# Pg5-Voltage_signal_condtioning.net
KiCad netlist of a schematic drawn in Altium Designer
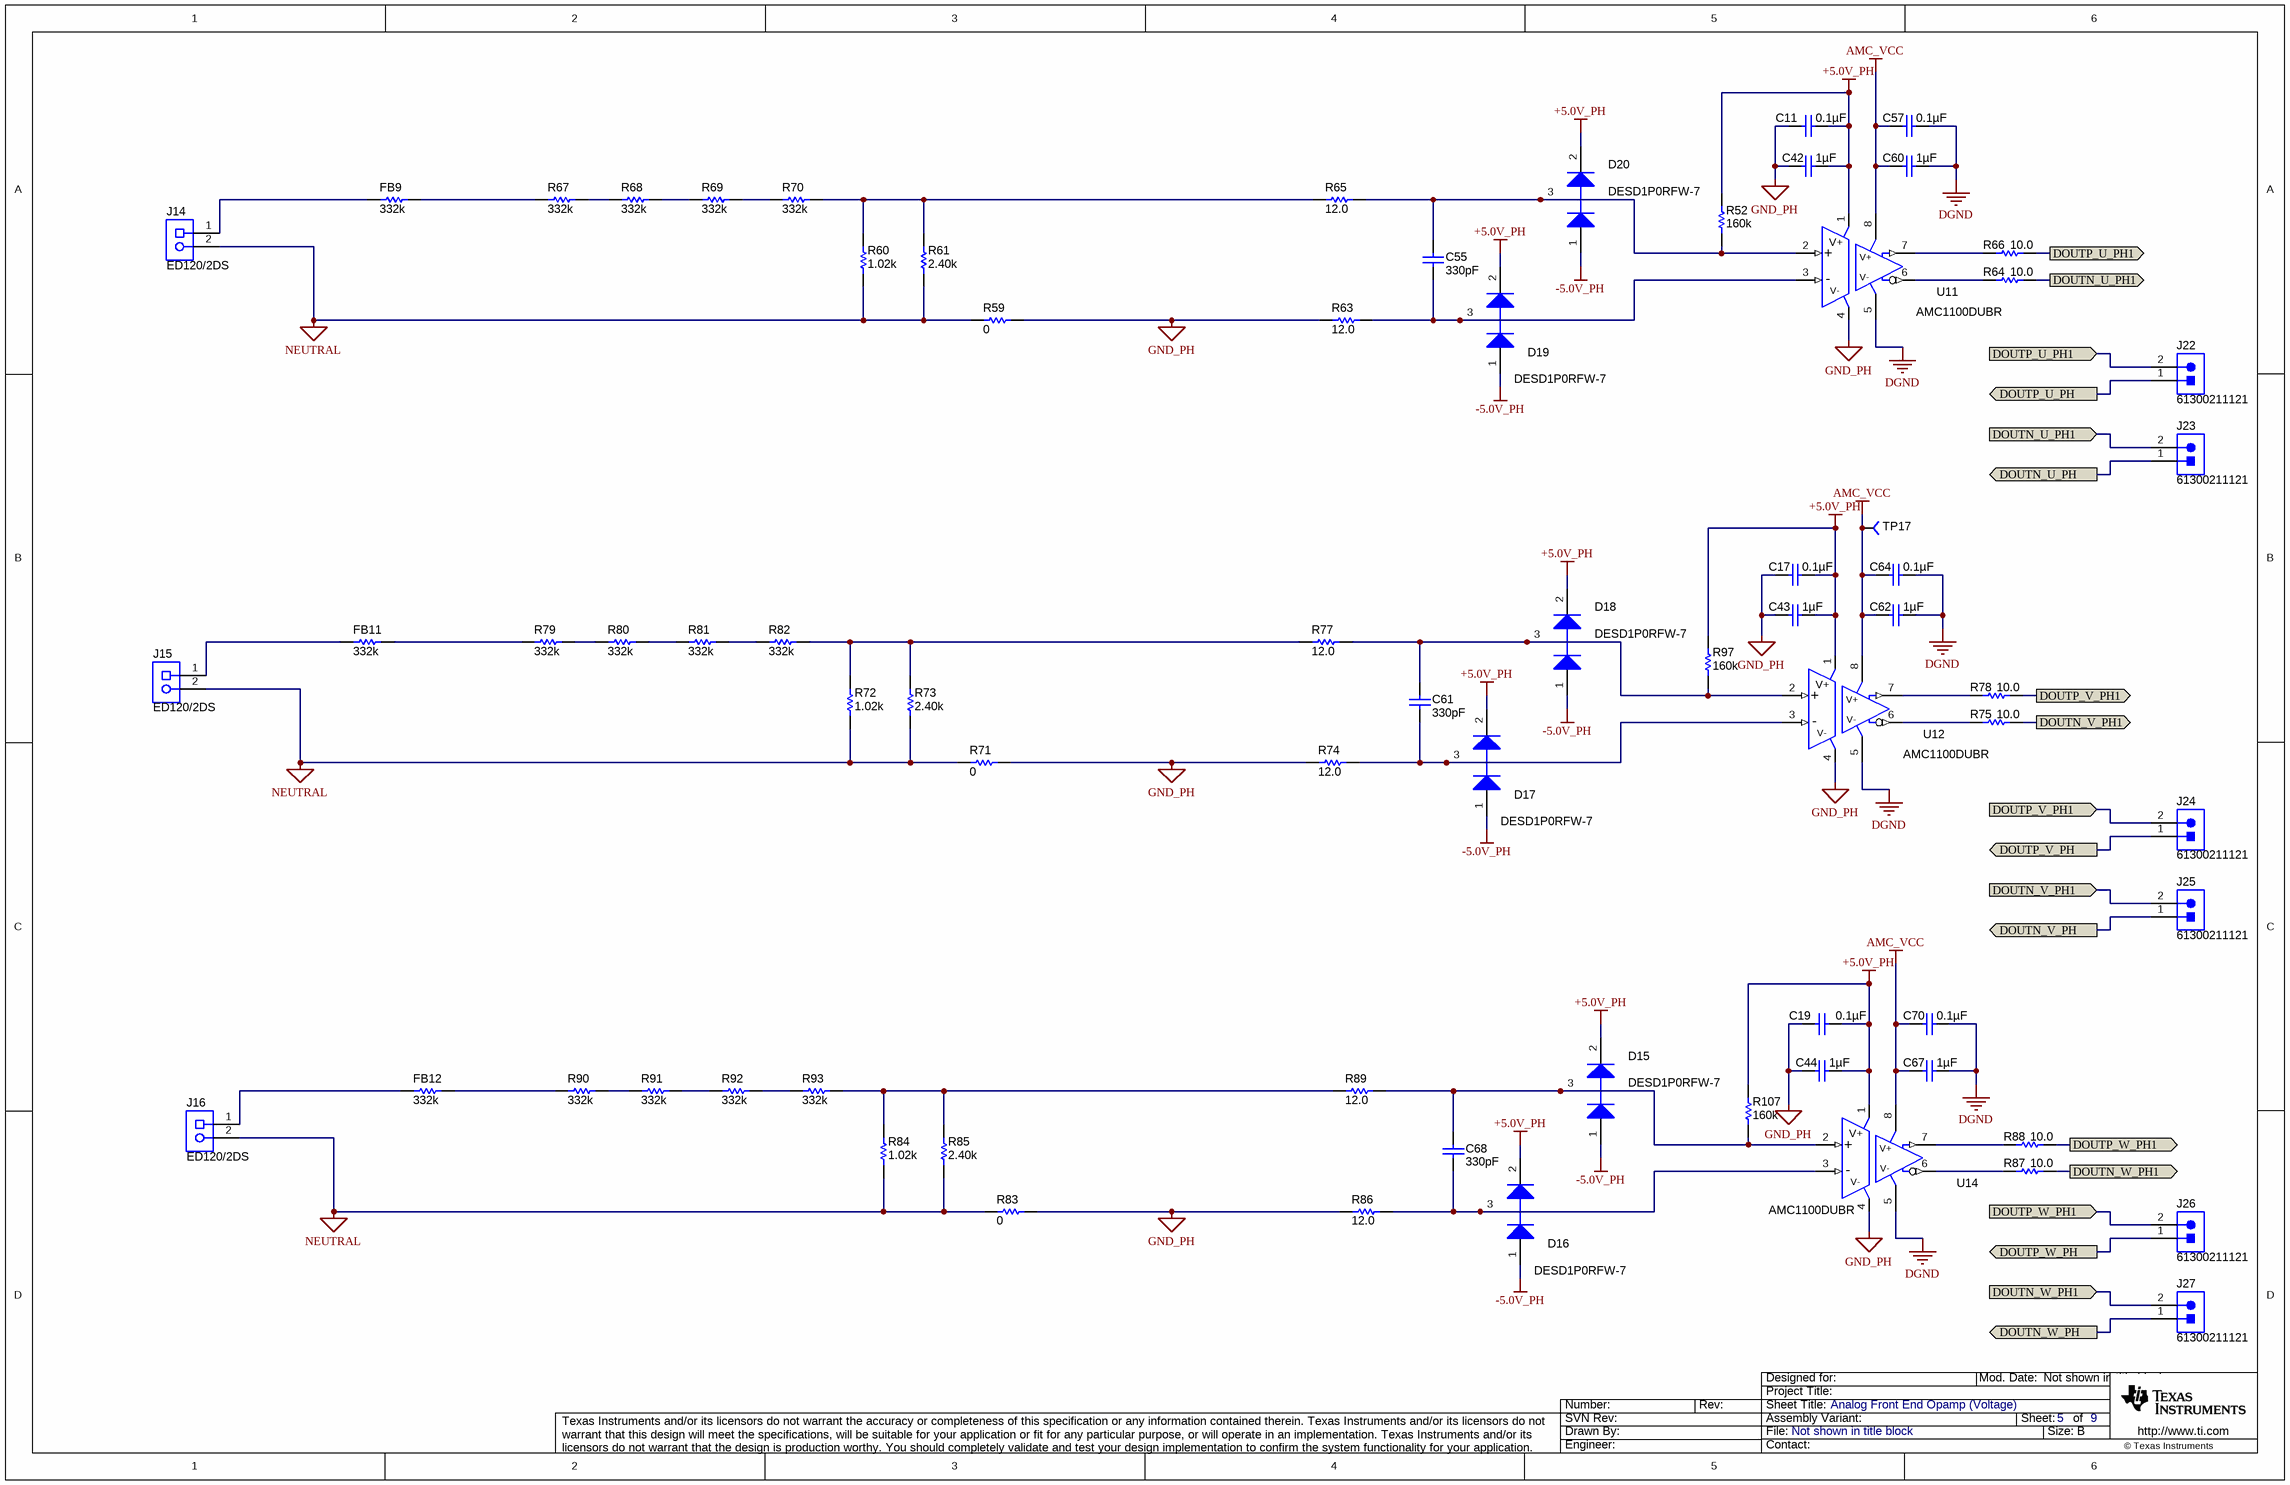
[diagram p0: Pg5-Voltage signal condtioning.SchDoc]

(export (version "E")
  (design (tool "Eeschema 10.0.6"))
  (components
    (comp (ref "C11")
      (value "~")
      (footprint "0603")
      (description "CAP, CERM, 0.1uF, 25V, +/-5%, X7R, 0603")
      (fields
        (field (name "PARTNUMBER") "06033C104JAT2A")
        (field (name "VALUEDISPLAYED") "0.1µF")
        (field (name "MANUFACTURER") "AVX")
        (field (name "PUBLISHER") "Texas Instruments")
      )
      (libsource (lib "Capacitor_Ceramic") (part "06033C104JAT2A"))
    )
    (comp (ref "C17")
      (value "~")
      (footprint "0603")
      (description "CAP, CERM, 0.1uF, 25V, +/-5%, X7R, 0603")
      (fields
        (field (name "PARTNUMBER") "06033C104JAT2A")
        (field (name "VALUEDISPLAYED") "0.1µF")
        (field (name "MANUFACTURER") "AVX")
        (field (name "PUBLISHER") "Texas Instruments")
      )
      (libsource (lib "Capacitor_Ceramic") (part "06033C104JAT2A"))
    )
    (comp (ref "C19")
      (value "~")
      (footprint "0603")
      (description "CAP, CERM, 0.1uF, 25V, +/-5%, X7R, 0603")
      (fields
        (field (name "PARTNUMBER") "06033C104JAT2A")
        (field (name "VALUEDISPLAYED") "0.1µF")
        (field (name "MANUFACTURER") "AVX")
        (field (name "PUBLISHER") "Texas Instruments")
      )
      (libsource (lib "Capacitor_Ceramic") (part "06033C104JAT2A"))
    )
    (comp (ref "C42")
      (value "GRM188R71C105KA12D")
      (footprint "0603")
      (description "CAP, CERM, 1 µF, 16 V, +/- 10%, X7R, 0603")
      (fields
        (field (name "VALUEDISPLAYED") "1µF")
        (field (name "MANUFACTURER") "MuRata")
        (field (name "PUBLISHER") "Texas Instruments")
      )
      (libsource (lib "Capacitor_Ceramic") (part "GRM188R71C105KA12D"))
    )
    (comp (ref "C43")
      (value "GRM188R71C105KA12D")
      (footprint "0603")
      (description "CAP, CERM, 1 µF, 16 V, +/- 10%, X7R, 0603")
      (fields
        (field (name "VALUEDISPLAYED") "1µF")
        (field (name "MANUFACTURER") "MuRata")
        (field (name "PUBLISHER") "Texas Instruments")
      )
      (libsource (lib "Capacitor_Ceramic") (part "GRM188R71C105KA12D"))
    )
    (comp (ref "C44")
      (value "GRM188R71C105KA12D")
      (footprint "0603")
      (description "CAP, CERM, 1 µF, 16 V, +/- 10%, X7R, 0603")
      (fields
        (field (name "VALUEDISPLAYED") "1µF")
        (field (name "MANUFACTURER") "MuRata")
        (field (name "PUBLISHER") "Texas Instruments")
      )
      (libsource (lib "Capacitor_Ceramic") (part "GRM188R71C105KA12D"))
    )
    (comp (ref "C55")
      (value "08055A331KAT2A")
      (footprint "0805_HV")
      (description "CAP, CERM, 330 pF, 50 V, +/- 10%, C0G/NP0, 0805")
      (fields
        (field (name "VALUEDISPLAYED") "330pF")
        (field (name "MANUFACTURER") "AVX")
        (field (name "PUBLISHER") "Texas Instruments")
      )
      (libsource (lib "Capacitor_Ceramic") (part "08055A331KAT2A"))
    )
    (comp (ref "C57")
      (value "~")
      (footprint "0603")
      (description "CAP, CERM, 0.1uF, 25V, +/-5%, X7R, 0603")
      (fields
        (field (name "PARTNUMBER") "06033C104JAT2A")
        (field (name "VALUEDISPLAYED") "0.1µF")
        (field (name "MANUFACTURER") "AVX")
        (field (name "PUBLISHER") "Texas Instruments")
      )
      (libsource (lib "Capacitor_Ceramic") (part "06033C104JAT2A"))
    )
    (comp (ref "C60")
      (value "GRM188R71C105KA12D")
      (footprint "0603")
      (description "CAP, CERM, 1 µF, 16 V, +/- 10%, X7R, 0603")
      (fields
        (field (name "VALUEDISPLAYED") "1µF")
        (field (name "MANUFACTURER") "MuRata")
        (field (name "PUBLISHER") "Texas Instruments")
      )
      (libsource (lib "Capacitor_Ceramic") (part "GRM188R71C105KA12D"))
    )
    (comp (ref "C61")
      (value "08055A331KAT2A")
      (footprint "0805_HV")
      (description "CAP, CERM, 330 pF, 50 V, +/- 10%, C0G/NP0, 0805")
      (fields
        (field (name "VALUEDISPLAYED") "330pF")
        (field (name "MANUFACTURER") "AVX")
        (field (name "PUBLISHER") "Texas Instruments")
      )
      (libsource (lib "Capacitor_Ceramic") (part "08055A331KAT2A"))
    )
    (comp (ref "C62")
      (value "GRM188R71C105KA12D")
      (footprint "0603")
      (description "CAP, CERM, 1 µF, 16 V, +/- 10%, X7R, 0603")
      (fields
        (field (name "VALUEDISPLAYED") "1µF")
        (field (name "MANUFACTURER") "MuRata")
        (field (name "PUBLISHER") "Texas Instruments")
      )
      (libsource (lib "Capacitor_Ceramic") (part "GRM188R71C105KA12D"))
    )
    (comp (ref "C64")
      (value "~")
      (footprint "0603")
      (description "CAP, CERM, 0.1uF, 25V, +/-5%, X7R, 0603")
      (fields
        (field (name "PARTNUMBER") "06033C104JAT2A")
        (field (name "VALUEDISPLAYED") "0.1µF")
        (field (name "MANUFACTURER") "AVX")
        (field (name "PUBLISHER") "Texas Instruments")
      )
      (libsource (lib "Capacitor_Ceramic") (part "06033C104JAT2A"))
    )
    (comp (ref "C67")
      (value "GRM188R71C105KA12D")
      (footprint "0603")
      (description "CAP, CERM, 1 µF, 16 V, +/- 10%, X7R, 0603")
      (fields
        (field (name "VALUEDISPLAYED") "1µF")
        (field (name "MANUFACTURER") "MuRata")
        (field (name "PUBLISHER") "Texas Instruments")
      )
      (libsource (lib "Capacitor_Ceramic") (part "GRM188R71C105KA12D"))
    )
    (comp (ref "C68")
      (value "08055A331KAT2A")
      (footprint "0805_HV")
      (description "CAP, CERM, 330 pF, 50 V, +/- 10%, C0G/NP0, 0805")
      (fields
        (field (name "VALUEDISPLAYED") "330pF")
        (field (name "MANUFACTURER") "AVX")
        (field (name "PUBLISHER") "Texas Instruments")
      )
      (libsource (lib "Capacitor_Ceramic") (part "08055A331KAT2A"))
    )
    (comp (ref "C70")
      (value "~")
      (footprint "0603")
      (description "CAP, CERM, 0.1uF, 25V, +/-5%, X7R, 0603")
      (fields
        (field (name "PARTNUMBER") "06033C104JAT2A")
        (field (name "VALUEDISPLAYED") "0.1µF")
        (field (name "MANUFACTURER") "AVX")
        (field (name "PUBLISHER") "Texas Instruments")
      )
      (libsource (lib "Capacitor_Ceramic") (part "06033C104JAT2A"))
    )
    (comp (ref "D15")
      (value "DESD1P0RFW-7")
      (footprint "SOT-323")
      (description "Diode, P-N, 70V, 0.2A, SOT-323")
      (fields (field (name "MANUFACTURER") "Diodes Inc") (field (name "PUBLISHER") "Texas Instruments"))
      (libsource (lib "Diode") (part "BAV99WT1G"))
    )
    (comp (ref "D16")
      (value "DESD1P0RFW-7")
      (footprint "SOT-323")
      (description "Diode, P-N, 70V, 0.2A, SOT-323")
      (fields (field (name "MANUFACTURER") "Diodes Inc") (field (name "PUBLISHER") "Texas Instruments"))
      (libsource (lib "Diode") (part "BAV99WT1G"))
    )
    (comp (ref "D17")
      (value "DESD1P0RFW-7")
      (footprint "SOT-323")
      (description "Diode, P-N, 70V, 0.2A, SOT-323")
      (fields (field (name "MANUFACTURER") "Diodes Inc") (field (name "PUBLISHER") "Texas Instruments"))
      (libsource (lib "Diode") (part "BAV99WT1G"))
    )
    (comp (ref "D18")
      (value "DESD1P0RFW-7")
      (footprint "SOT-323")
      (description "Diode, P-N, 70V, 0.2A, SOT-323")
      (fields (field (name "MANUFACTURER") "Diodes Inc") (field (name "PUBLISHER") "Texas Instruments"))
      (libsource (lib "Diode") (part "BAV99WT1G"))
    )
    (comp (ref "D19")
      (value "DESD1P0RFW-7")
      (footprint "SOT-323")
      (description "Diode, P-N, 70V, 0.2A, SOT-323")
      (fields (field (name "MANUFACTURER") "Diodes Inc") (field (name "PUBLISHER") "Texas Instruments"))
      (libsource (lib "Diode") (part "BAV99WT1G"))
    )
    (comp (ref "D20")
      (value "DESD1P0RFW-7")
      (footprint "SOT-323")
      (description "Diode, P-N, 70V, 0.2A, SOT-323")
      (fields (field (name "MANUFACTURER") "Diodes Inc") (field (name "PUBLISHER") "Texas Instruments"))
      (libsource (lib "Diode") (part "BAV99WT1G"))
    )
    (comp (ref "FB9")
      (value "ERJ-8ENF3323V")
      (footprint "1206")
      (description "RES, 332 k, 1%, 0.25 W, 1206")
      (fields
        (field (name "VALUEDISPLAYED") "332k")
        (field (name "MANUFACTURER") "Panasonic")
        (field (name "PUBLISHER") "Texas Instruments")
      )
      (libsource (lib "Resistor_1206") (part "ERJ-8ENF3323V"))
    )
    (comp (ref "FB11")
      (value "ERJ-8ENF3323V")
      (footprint "1206")
      (description "RES, 332 k, 1%, 0.25 W, 1206")
      (fields
        (field (name "VALUEDISPLAYED") "332k")
        (field (name "MANUFACTURER") "Panasonic")
        (field (name "PUBLISHER") "Texas Instruments")
      )
      (libsource (lib "Resistor_1206") (part "ERJ-8ENF3323V"))
    )
    (comp (ref "FB12")
      (value "ERJ-8ENF3323V")
      (footprint "1206")
      (description "RES, 332 k, 1%, 0.25 W, 1206")
      (fields
        (field (name "VALUEDISPLAYED") "332k")
        (field (name "MANUFACTURER") "Panasonic")
        (field (name "PUBLISHER") "Texas Instruments")
      )
      (libsource (lib "Resistor_1206") (part "ERJ-8ENF3323V"))
    )
    (comp (ref "J14")
      (value "ED120/2DS")
      (footprint "CONN_ED120-2DS")
      (description "TERMINAL BLOCK 5.08MM VERT 2POS, TH")
      (fields
        (field (name "MANUFACTURER") "On-Shore Technology")
        (field (name "SYMBOLCREATOR") "a0412235")
        (field (name "PUBLISHER") "Texas Instruments")
      )
      (libsource (lib "Connectors") (part "ED120/2DS"))
    )
    (comp (ref "J15")
      (value "ED120/2DS")
      (footprint "CONN_ED120-2DS")
      (description "TERMINAL BLOCK 5.08MM VERT 2POS, TH")
      (fields
        (field (name "MANUFACTURER") "On-Shore Technology")
        (field (name "SYMBOLCREATOR") "a0412235")
        (field (name "PUBLISHER") "Texas Instruments")
      )
      (libsource (lib "Connectors") (part "ED120/2DS"))
    )
    (comp (ref "J16")
      (value "ED120/2DS")
      (footprint "CONN_ED120-2DS")
      (description "TERMINAL BLOCK 5.08MM VERT 2POS, TH")
      (fields
        (field (name "MANUFACTURER") "On-Shore Technology")
        (field (name "SYMBOLCREATOR") "a0412235")
        (field (name "PUBLISHER") "Texas Instruments")
      )
      (libsource (lib "Connectors") (part "ED120/2DS"))
    )
    (comp (ref "J22")
      (value "61300211121")
      (footprint "WURTH_61300211121")
      (description "Header, 2.54 mm, 2x1, Gold, TH")
      (fields
        (field (name "MANUFACTURER") "Wurth Elektronik eiSos")
        (field (name "SYMBOLCREATOR") "a0412235")
        (field (name "PUBLISHER") "Texas Instruments")
      )
      (libsource (lib "Connectors") (part "61300211121"))
    )
    (comp (ref "J23")
      (value "61300211121")
      (footprint "WURTH_61300211121")
      (description "Header, 2.54 mm, 2x1, Gold, TH")
      (fields
        (field (name "MANUFACTURER") "Wurth Elektronik eiSos")
        (field (name "SYMBOLCREATOR") "a0412235")
        (field (name "PUBLISHER") "Texas Instruments")
      )
      (libsource (lib "Connectors") (part "61300211121"))
    )
    (comp (ref "J24")
      (value "61300211121")
      (footprint "WURTH_61300211121")
      (description "Header, 2.54 mm, 2x1, Gold, TH")
      (fields
        (field (name "MANUFACTURER") "Wurth Elektronik eiSos")
        (field (name "SYMBOLCREATOR") "a0412235")
        (field (name "PUBLISHER") "Texas Instruments")
      )
      (libsource (lib "Connectors") (part "61300211121"))
    )
    (comp (ref "J25")
      (value "61300211121")
      (footprint "WURTH_61300211121")
      (description "Header, 2.54 mm, 2x1, Gold, TH")
      (fields
        (field (name "MANUFACTURER") "Wurth Elektronik eiSos")
        (field (name "SYMBOLCREATOR") "a0412235")
        (field (name "PUBLISHER") "Texas Instruments")
      )
      (libsource (lib "Connectors") (part "61300211121"))
    )
    (comp (ref "J26")
      (value "61300211121")
      (footprint "WURTH_61300211121")
      (description "Header, 2.54 mm, 2x1, Gold, TH")
      (fields
        (field (name "MANUFACTURER") "Wurth Elektronik eiSos")
        (field (name "SYMBOLCREATOR") "a0412235")
        (field (name "PUBLISHER") "Texas Instruments")
      )
      (libsource (lib "Connectors") (part "61300211121"))
    )
    (comp (ref "J27")
      (value "61300211121")
      (footprint "WURTH_61300211121")
      (description "Header, 2.54 mm, 2x1, Gold, TH")
      (fields
        (field (name "MANUFACTURER") "Wurth Elektronik eiSos")
        (field (name "SYMBOLCREATOR") "a0412235")
        (field (name "PUBLISHER") "Texas Instruments")
      )
      (libsource (lib "Connectors") (part "61300211121"))
    )
    (comp (ref "R52")
      (value "CRCW0603160KFKEA")
      (footprint "0603")
      (description "RES, 160 k, 1%, 0.1 W, 0603")
      (fields
        (field (name "MANUFACTURER") "Vishay-Dale")
        (field (name "VALUEDISPLAYED") "160k")
        (field (name "PUBLISHER") "Texas Instruments")
      )
      (libsource (lib "Resistor_0603") (part "CRCW0603160KFKEA"))
    )
    (comp (ref "R59")
      (value "0")
      (footprint "0805_HV")
      (description "RES, 0 ohm, 5%, 0.125W, 0805")
      (fields
        (field (name "PARTNUMBER") "CRCW08050000Z0EA")
        (field (name "MANUFACTURER") "Vishay-Dale")
        (field (name "PUBLISHER") "Texas Instruments")
      )
      (libsource (lib "Resistor_0805") (part "CRCW08050000Z0EA"))
    )
    (comp (ref "R60")
      (value "RC1206FR-071K02L")
      (footprint "1206")
      (description "RES SMD 1.02K OHM 1% 1/4W 1206")
      (fields
        (field (name "VALUEDISPLAYED") "1.02k")
        (field (name "MANUFACTURER") "Yageo America")
        (field (name "PUBLISHER") "Texas Instruments")
      )
      (libsource (lib "Resistor_1206") (part "RC1206FR-072K4L"))
    )
    (comp (ref "R61")
      (value "RC1206FR-072K4L")
      (footprint "1206")
      (description "RES, 2.40 k, 1%, 0.25 W, 1206")
      (fields
        (field (name "VALUEDISPLAYED") "2.40k")
        (field (name "MANUFACTURER") "Yageo America")
        (field (name "PUBLISHER") "Texas Instruments")
      )
      (libsource (lib "Resistor_1206") (part "RC1206FR-072K4L"))
    )
    (comp (ref "R63")
      (value "RC0603FR-0712RL")
      (footprint "0603")
      (description "RES, 12.0, 1%, 0.1 W, 0603")
      (fields
        (field (name "VALUEDISPLAYED") "12.0")
        (field (name "MANUFACTURER") "Yageo America")
        (field (name "PUBLISHER") "Texas Instruments")
      )
      (libsource (lib "Resistor_0603") (part "RC0603FR-0712RL"))
    )
    (comp (ref "R64")
      (value "10.0")
      (footprint "0603")
      (description "RES, 10.0 ohm, 1%, 0.1W, 0603")
      (fields
        (field (name "PARTNUMBER") "CRCW060310R0FKEA")
        (field (name "MANUFACTURER") "Vishay-Dale")
        (field (name "PUBLISHER") "Texas Instruments")
      )
      (libsource (lib "Resistor_0603") (part "CRCW060310R0FKEA"))
    )
    (comp (ref "R65")
      (value "RC0603FR-0712RL")
      (footprint "0603")
      (description "RES, 12.0, 1%, 0.1 W, 0603")
      (fields
        (field (name "VALUEDISPLAYED") "12.0")
        (field (name "MANUFACTURER") "Yageo America")
        (field (name "PUBLISHER") "Texas Instruments")
      )
      (libsource (lib "Resistor_0603") (part "RC0603FR-0712RL"))
    )
    (comp (ref "R66")
      (value "10.0")
      (footprint "0603")
      (description "RES, 10.0 ohm, 1%, 0.1W, 0603")
      (fields
        (field (name "PARTNUMBER") "CRCW060310R0FKEA")
        (field (name "MANUFACTURER") "Vishay-Dale")
        (field (name "PUBLISHER") "Texas Instruments")
      )
      (libsource (lib "Resistor_0603") (part "CRCW060310R0FKEA"))
    )
    (comp (ref "R67")
      (value "ERJ-8ENF3323V")
      (footprint "1206")
      (description "RES, 332 k, 1%, 0.25 W, 1206")
      (fields
        (field (name "VALUEDISPLAYED") "332k")
        (field (name "MANUFACTURER") "Panasonic")
        (field (name "PUBLISHER") "Texas Instruments")
      )
      (libsource (lib "Resistor_1206") (part "ERJ-8ENF3323V"))
    )
    (comp (ref "R68")
      (value "ERJ-8ENF3323V")
      (footprint "1206")
      (description "RES, 332 k, 1%, 0.25 W, 1206")
      (fields
        (field (name "VALUEDISPLAYED") "332k")
        (field (name "MANUFACTURER") "Panasonic")
        (field (name "PUBLISHER") "Texas Instruments")
      )
      (libsource (lib "Resistor_1206") (part "ERJ-8ENF3323V"))
    )
    (comp (ref "R69")
      (value "ERJ-8ENF3323V")
      (footprint "1206")
      (description "RES, 332 k, 1%, 0.25 W, 1206")
      (fields
        (field (name "VALUEDISPLAYED") "332k")
        (field (name "MANUFACTURER") "Panasonic")
        (field (name "PUBLISHER") "Texas Instruments")
      )
      (libsource (lib "Resistor_1206") (part "ERJ-8ENF3323V"))
    )
    (comp (ref "R70")
      (value "ERJ-8ENF3323V")
      (footprint "1206")
      (description "RES, 332 k, 1%, 0.25 W, 1206")
      (fields
        (field (name "VALUEDISPLAYED") "332k")
        (field (name "MANUFACTURER") "Panasonic")
        (field (name "PUBLISHER") "Texas Instruments")
      )
      (libsource (lib "Resistor_1206") (part "ERJ-8ENF3323V"))
    )
    (comp (ref "R71")
      (value "0")
      (footprint "0805_HV")
      (description "RES, 0 ohm, 5%, 0.125W, 0805")
      (fields
        (field (name "PARTNUMBER") "CRCW08050000Z0EA")
        (field (name "MANUFACTURER") "Vishay-Dale")
        (field (name "PUBLISHER") "Texas Instruments")
      )
      (libsource (lib "Resistor_0805") (part "CRCW08050000Z0EA"))
    )
    (comp (ref "R72")
      (value "RC1206FR-071K02L")
      (footprint "1206")
      (description "RES SMD 1.02K OHM 1% 1/4W 1206")
      (fields
        (field (name "VALUEDISPLAYED") "1.02k")
        (field (name "MANUFACTURER") "Yageo America")
        (field (name "PUBLISHER") "Texas Instruments")
      )
      (libsource (lib "Resistor_1206") (part "RC1206FR-072K4L"))
    )
    (comp (ref "R73")
      (value "RC1206FR-072K4L")
      (footprint "1206")
      (description "RES, 2.40 k, 1%, 0.25 W, 1206")
      (fields
        (field (name "VALUEDISPLAYED") "2.40k")
        (field (name "MANUFACTURER") "Yageo America")
        (field (name "PUBLISHER") "Texas Instruments")
      )
      (libsource (lib "Resistor_1206") (part "RC1206FR-072K4L"))
    )
    (comp (ref "R74")
      (value "RC0603FR-0712RL")
      (footprint "0603")
      (description "RES, 12.0, 1%, 0.1 W, 0603")
      (fields
        (field (name "VALUEDISPLAYED") "12.0")
        (field (name "MANUFACTURER") "Yageo America")
        (field (name "PUBLISHER") "Texas Instruments")
      )
      (libsource (lib "Resistor_0603") (part "RC0603FR-0712RL"))
    )
    (comp (ref "R75")
      (value "10.0")
      (footprint "0603")
      (description "RES, 10.0 ohm, 1%, 0.1W, 0603")
      (fields
        (field (name "PARTNUMBER") "CRCW060310R0FKEA")
        (field (name "MANUFACTURER") "Vishay-Dale")
        (field (name "PUBLISHER") "Texas Instruments")
      )
      (libsource (lib "Resistor_0603") (part "CRCW060310R0FKEA"))
    )
    (comp (ref "R77")
      (value "RC0603FR-0712RL")
      (footprint "0603")
      (description "RES, 12.0, 1%, 0.1 W, 0603")
      (fields
        (field (name "VALUEDISPLAYED") "12.0")
        (field (name "MANUFACTURER") "Yageo America")
        (field (name "PUBLISHER") "Texas Instruments")
      )
      (libsource (lib "Resistor_0603") (part "RC0603FR-0712RL"))
    )
    (comp (ref "R78")
      (value "10.0")
      (footprint "0603")
      (description "RES, 10.0 ohm, 1%, 0.1W, 0603")
      (fields
        (field (name "PARTNUMBER") "CRCW060310R0FKEA")
        (field (name "MANUFACTURER") "Vishay-Dale")
        (field (name "PUBLISHER") "Texas Instruments")
      )
      (libsource (lib "Resistor_0603") (part "CRCW060310R0FKEA"))
    )
    (comp (ref "R79")
      (value "ERJ-8ENF3323V")
      (footprint "1206")
      (description "RES, 332 k, 1%, 0.25 W, 1206")
      (fields
        (field (name "VALUEDISPLAYED") "332k")
        (field (name "MANUFACTURER") "Panasonic")
        (field (name "PUBLISHER") "Texas Instruments")
      )
      (libsource (lib "Resistor_1206") (part "ERJ-8ENF3323V"))
    )
    (comp (ref "R80")
      (value "ERJ-8ENF3323V")
      (footprint "1206")
      (description "RES, 332 k, 1%, 0.25 W, 1206")
      (fields
        (field (name "VALUEDISPLAYED") "332k")
        (field (name "MANUFACTURER") "Panasonic")
        (field (name "PUBLISHER") "Texas Instruments")
      )
      (libsource (lib "Resistor_1206") (part "ERJ-8ENF3323V"))
    )
    (comp (ref "R81")
      (value "ERJ-8ENF3323V")
      (footprint "1206")
      (description "RES, 332 k, 1%, 0.25 W, 1206")
      (fields
        (field (name "VALUEDISPLAYED") "332k")
        (field (name "MANUFACTURER") "Panasonic")
        (field (name "PUBLISHER") "Texas Instruments")
      )
      (libsource (lib "Resistor_1206") (part "ERJ-8ENF3323V"))
    )
    (comp (ref "R82")
      (value "ERJ-8ENF3323V")
      (footprint "1206")
      (description "RES, 332 k, 1%, 0.25 W, 1206")
      (fields
        (field (name "VALUEDISPLAYED") "332k")
        (field (name "MANUFACTURER") "Panasonic")
        (field (name "PUBLISHER") "Texas Instruments")
      )
      (libsource (lib "Resistor_1206") (part "ERJ-8ENF3323V"))
    )
    (comp (ref "R83")
      (value "0")
      (footprint "0805_HV")
      (description "RES, 0 ohm, 5%, 0.125W, 0805")
      (fields
        (field (name "PARTNUMBER") "CRCW08050000Z0EA")
        (field (name "MANUFACTURER") "Vishay-Dale")
        (field (name "PUBLISHER") "Texas Instruments")
      )
      (libsource (lib "Resistor_0805") (part "CRCW08050000Z0EA"))
    )
    (comp (ref "R84")
      (value "RC1206FR-071K02L")
      (footprint "1206")
      (description "RES SMD 1.02K OHM 1% 1/4W 1206")
      (fields
        (field (name "VALUEDISPLAYED") "1.02k")
        (field (name "MANUFACTURER") "Yageo America")
        (field (name "PUBLISHER") "Texas Instruments")
      )
      (libsource (lib "Resistor_1206") (part "RC1206FR-072K4L"))
    )
    (comp (ref "R85")
      (value "RC1206FR-072K4L")
      (footprint "1206")
      (description "RES, 2.40 k, 1%, 0.25 W, 1206")
      (fields
        (field (name "VALUEDISPLAYED") "2.40k")
        (field (name "MANUFACTURER") "Yageo America")
        (field (name "PUBLISHER") "Texas Instruments")
      )
      (libsource (lib "Resistor_1206") (part "RC1206FR-072K4L"))
    )
    (comp (ref "R86")
      (value "RC0603FR-0712RL")
      (footprint "0603")
      (description "RES, 12.0, 1%, 0.1 W, 0603")
      (fields
        (field (name "VALUEDISPLAYED") "12.0")
        (field (name "MANUFACTURER") "Yageo America")
        (field (name "PUBLISHER") "Texas Instruments")
      )
      (libsource (lib "Resistor_0603") (part "RC0603FR-0712RL"))
    )
    (comp (ref "R87")
      (value "10.0")
      (footprint "0603")
      (description "RES, 10.0 ohm, 1%, 0.1W, 0603")
      (fields
        (field (name "PARTNUMBER") "CRCW060310R0FKEA")
        (field (name "MANUFACTURER") "Vishay-Dale")
        (field (name "PUBLISHER") "Texas Instruments")
      )
      (libsource (lib "Resistor_0603") (part "CRCW060310R0FKEA"))
    )
    (comp (ref "R88")
      (value "10.0")
      (footprint "0603")
      (description "RES, 10.0 ohm, 1%, 0.1W, 0603")
      (fields
        (field (name "PARTNUMBER") "CRCW060310R0FKEA")
        (field (name "MANUFACTURER") "Vishay-Dale")
        (field (name "PUBLISHER") "Texas Instruments")
      )
      (libsource (lib "Resistor_0603") (part "CRCW060310R0FKEA"))
    )
    (comp (ref "R89")
      (value "RC0603FR-0712RL")
      (footprint "0603")
      (description "RES, 12.0, 1%, 0.1 W, 0603")
      (fields
        (field (name "VALUEDISPLAYED") "12.0")
        (field (name "MANUFACTURER") "Yageo America")
        (field (name "PUBLISHER") "Texas Instruments")
      )
      (libsource (lib "Resistor_0603") (part "RC0603FR-0712RL"))
    )
    (comp (ref "R90")
      (value "ERJ-8ENF3323V")
      (footprint "1206")
      (description "RES, 332 k, 1%, 0.25 W, 1206")
      (fields
        (field (name "VALUEDISPLAYED") "332k")
        (field (name "MANUFACTURER") "Panasonic")
        (field (name "PUBLISHER") "Texas Instruments")
      )
      (libsource (lib "Resistor_1206") (part "ERJ-8ENF3323V"))
    )
    (comp (ref "R91")
      (value "ERJ-8ENF3323V")
      (footprint "1206")
      (description "RES, 332 k, 1%, 0.25 W, 1206")
      (fields
        (field (name "VALUEDISPLAYED") "332k")
        (field (name "MANUFACTURER") "Panasonic")
        (field (name "PUBLISHER") "Texas Instruments")
      )
      (libsource (lib "Resistor_1206") (part "ERJ-8ENF3323V"))
    )
    (comp (ref "R92")
      (value "ERJ-8ENF3323V")
      (footprint "1206")
      (description "RES, 332 k, 1%, 0.25 W, 1206")
      (fields
        (field (name "VALUEDISPLAYED") "332k")
        (field (name "MANUFACTURER") "Panasonic")
        (field (name "PUBLISHER") "Texas Instruments")
      )
      (libsource (lib "Resistor_1206") (part "ERJ-8ENF3323V"))
    )
    (comp (ref "R93")
      (value "ERJ-8ENF3323V")
      (footprint "1206")
      (description "RES, 332 k, 1%, 0.25 W, 1206")
      (fields
        (field (name "VALUEDISPLAYED") "332k")
        (field (name "MANUFACTURER") "Panasonic")
        (field (name "PUBLISHER") "Texas Instruments")
      )
      (libsource (lib "Resistor_1206") (part "ERJ-8ENF3323V"))
    )
    (comp (ref "R97")
      (value "CRCW0603160KFKEA")
      (footprint "0603")
      (description "RES, 160 k, 1%, 0.1 W, 0603")
      (fields
        (field (name "MANUFACTURER") "Vishay-Dale")
        (field (name "VALUEDISPLAYED") "160k")
        (field (name "PUBLISHER") "Texas Instruments")
      )
      (libsource (lib "Resistor_0603") (part "CRCW0603160KFKEA"))
    )
    (comp (ref "R107")
      (value "CRCW0603160KFKEA")
      (footprint "0603")
      (description "RES, 160 k, 1%, 0.1 W, 0603")
      (fields
        (field (name "MANUFACTURER") "Vishay-Dale")
        (field (name "VALUEDISPLAYED") "160k")
        (field (name "PUBLISHER") "Texas Instruments")
      )
      (libsource (lib "Resistor_0603") (part "CRCW0603160KFKEA"))
    )
    (comp (ref "TP17")
      (value "~")
      (footprint "TP-040_RND")
      (description "Test Point, O.040 Hole")
      (fields (field (name "MANUFACTURER") "STD"))
      (libsource (lib "PADSlegacy_Hardware") (part "TP-040_RND"))
    )
    (comp (ref "U11")
      (value "AMC1100DUBR")
      (footprint "DUB0008A_N")
      (description "Fully-Differential Isolation Amplifier, DUB0008A")
      (fields
        (field (name "ALTERNATE PARTNUMBER") "AMC1100DUB")
        (field (name "MANUFACTURER") "Texas Instruments")
        (field (name "SYMBOLCREATOR") "a0411947")
        (field (name "PUBLISHER") "Texas Instruments")
      )
      (libsource (lib "TI_Pre_RTM") (part "AMC1100DUBR"))
    )
    (comp (ref "U12")
      (value "AMC1100DUBR")
      (footprint "DUB0008A_N")
      (description "Fully-Differential Isolation Amplifier, DUB0008A")
      (fields
        (field (name "ALTERNATE PARTNUMBER") "AMC1100DUB")
        (field (name "MANUFACTURER") "Texas Instruments")
        (field (name "SYMBOLCREATOR") "a0411947")
        (field (name "PUBLISHER") "Texas Instruments")
      )
      (libsource (lib "TI_Pre_RTM") (part "AMC1100DUBR"))
    )
    (comp (ref "U14")
      (value "AMC1100DUBR")
      (footprint "DUB0008A_N")
      (description "Fully-Differential Isolation Amplifier, DUB0008A")
      (fields
        (field (name "ALTERNATE PARTNUMBER") "AMC1100DUB")
        (field (name "MANUFACTURER") "Texas Instruments")
        (field (name "SYMBOLCREATOR") "a0411947")
        (field (name "PUBLISHER") "Texas Instruments")
      )
      (libsource (lib "TI_Pre_RTM") (part "AMC1100DUBR"))
    )
  )
  (nets
    (net (code "1") (name "+5.0V_PH") (class "Default")
      (node (ref "C11") (pin "1") (pinfunction "1_1") (pintype "passive"))
      (node (ref "C17") (pin "1") (pinfunction "1_1") (pintype "passive"))
      (node (ref "C19") (pin "1") (pinfunction "1_1") (pintype "passive"))
      (node (ref "C42") (pin "2") (pinfunction "2_2") (pintype "passive"))
      (node (ref "C43") (pin "2") (pinfunction "2_2") (pintype "passive"))
      (node (ref "C44") (pin "2") (pinfunction "2_2") (pintype "passive"))
      (node (ref "D15") (pin "2") (pinfunction "K_2") (pintype "passive"))
      (node (ref "D16") (pin "2") (pinfunction "K_2") (pintype "passive"))
      (node (ref "D17") (pin "2") (pinfunction "K_2") (pintype "passive"))
      (node (ref "D18") (pin "2") (pinfunction "K_2") (pintype "passive"))
      (node (ref "D19") (pin "2") (pinfunction "K_2") (pintype "passive"))
      (node (ref "D20") (pin "2") (pinfunction "K_2") (pintype "passive"))
      (node (ref "R107") (pin "2") (pinfunction "2_2") (pintype "passive"))
      (node (ref "R52") (pin "2") (pinfunction "2_2") (pintype "passive"))
      (node (ref "R97") (pin "2") (pinfunction "2_2") (pintype "passive"))
      (node (ref "U11") (pin "1") (pinfunction "VDD1_1") (pintype "power_in"))
      (node (ref "U12") (pin "1") (pinfunction "VDD1_1") (pintype "power_in"))
      (node (ref "U14") (pin "1") (pinfunction "VDD1_1") (pintype "power_in"))
    )
    (net (code "2") (name "-5.0V_PH") (class "Default")
      (node (ref "D15") (pin "1") (pinfunction "A_1") (pintype "passive"))
      (node (ref "D16") (pin "1") (pinfunction "A_1") (pintype "passive"))
      (node (ref "D17") (pin "1") (pinfunction "A_1") (pintype "passive"))
      (node (ref "D18") (pin "1") (pinfunction "A_1") (pintype "passive"))
      (node (ref "D19") (pin "1") (pinfunction "A_1") (pintype "passive"))
      (node (ref "D20") (pin "1") (pinfunction "A_1") (pintype "passive"))
    )
    (net (code "3") (name "/DOUTN_U_PH") (class "Default")
      (node (ref "J23") (pin "1") (pinfunction "1_1") (pintype "passive"))
    )
    (net (code "4") (name "/DOUTN_U_PH1") (class "Default")
      (node (ref "J23") (pin "2") (pinfunction "2_2") (pintype "passive"))
      (node (ref "R64") (pin "2") (pinfunction "2_2") (pintype "passive"))
    )
    (net (code "5") (name "/DOUTN_V_PH") (class "Default")
      (node (ref "J25") (pin "1") (pinfunction "1_1") (pintype "passive"))
    )
    (net (code "6") (name "/DOUTN_V_PH1") (class "Default")
      (node (ref "J25") (pin "2") (pinfunction "2_2") (pintype "passive"))
      (node (ref "R75") (pin "2") (pinfunction "2_2") (pintype "passive"))
    )
    (net (code "7") (name "/DOUTN_W_PH") (class "Default")
      (node (ref "J27") (pin "1") (pinfunction "1_1") (pintype "passive"))
    )
    (net (code "8") (name "/DOUTN_W_PH1") (class "Default")
      (node (ref "J27") (pin "2") (pinfunction "2_2") (pintype "passive"))
      (node (ref "R87") (pin "2") (pinfunction "2_2") (pintype "passive"))
    )
    (net (code "9") (name "/DOUTP_U_PH") (class "Default")
      (node (ref "J22") (pin "1") (pinfunction "1_1") (pintype "passive"))
    )
    (net (code "10") (name "/DOUTP_U_PH1") (class "Default")
      (node (ref "J22") (pin "2") (pinfunction "2_2") (pintype "passive"))
      (node (ref "R66") (pin "2") (pinfunction "2_2") (pintype "passive"))
    )
    (net (code "11") (name "/DOUTP_V_PH") (class "Default")
      (node (ref "J24") (pin "1") (pinfunction "1_1") (pintype "passive"))
    )
    (net (code "12") (name "/DOUTP_V_PH1") (class "Default")
      (node (ref "J24") (pin "2") (pinfunction "2_2") (pintype "passive"))
      (node (ref "R78") (pin "2") (pinfunction "2_2") (pintype "passive"))
    )
    (net (code "13") (name "/DOUTP_W_PH") (class "Default")
      (node (ref "J26") (pin "1") (pinfunction "1_1") (pintype "passive"))
    )
    (net (code "14") (name "/DOUTP_W_PH1") (class "Default")
      (node (ref "J26") (pin "2") (pinfunction "2_2") (pintype "passive"))
      (node (ref "R88") (pin "2") (pinfunction "2_2") (pintype "passive"))
    )
    (net (code "15") (name "AMC_VCC") (class "Default")
      (node (ref "C57") (pin "2") (pinfunction "2_2") (pintype "passive"))
      (node (ref "C60") (pin "1") (pinfunction "1_1") (pintype "passive"))
      (node (ref "C62") (pin "1") (pinfunction "1_1") (pintype "passive"))
      (node (ref "C64") (pin "2") (pinfunction "2_2") (pintype "passive"))
      (node (ref "C67") (pin "1") (pinfunction "1_1") (pintype "passive"))
      (node (ref "C70") (pin "2") (pinfunction "2_2") (pintype "passive"))
      (node (ref "TP17") (pin "1") (pinfunction "1_1") (pintype "passive"))
      (node (ref "U11") (pin "8") (pinfunction "VDD2_8") (pintype "power_in"))
      (node (ref "U12") (pin "8") (pinfunction "VDD2_8") (pintype "power_in"))
      (node (ref "U14") (pin "8") (pinfunction "VDD2_8") (pintype "power_in"))
    )
    (net (code "16") (name "DGND") (class "Default")
      (node (ref "C57") (pin "1") (pinfunction "1_1") (pintype "passive"))
      (node (ref "C60") (pin "2") (pinfunction "2_2") (pintype "passive"))
      (node (ref "C62") (pin "2") (pinfunction "2_2") (pintype "passive"))
      (node (ref "C64") (pin "1") (pinfunction "1_1") (pintype "passive"))
      (node (ref "C67") (pin "2") (pinfunction "2_2") (pintype "passive"))
      (node (ref "C70") (pin "1") (pinfunction "1_1") (pintype "passive"))
      (node (ref "U11") (pin "5") (pinfunction "GND2_5") (pintype "power_in"))
      (node (ref "U12") (pin "5") (pinfunction "GND2_5") (pintype "power_in"))
      (node (ref "U14") (pin "5") (pinfunction "GND2_5") (pintype "power_in"))
    )
    (net (code "17") (name "GND_PH") (class "Default")
      (node (ref "C11") (pin "2") (pinfunction "2_2") (pintype "passive"))
      (node (ref "C17") (pin "2") (pinfunction "2_2") (pintype "passive"))
      (node (ref "C19") (pin "2") (pinfunction "2_2") (pintype "passive"))
      (node (ref "C42") (pin "1") (pinfunction "1_1") (pintype "passive"))
      (node (ref "C43") (pin "1") (pinfunction "1_1") (pintype "passive"))
      (node (ref "C44") (pin "1") (pinfunction "1_1") (pintype "passive"))
      (node (ref "R59") (pin "2") (pinfunction "2_2") (pintype "passive"))
      (node (ref "R63") (pin "1") (pinfunction "1_1") (pintype "passive"))
      (node (ref "R71") (pin "2") (pinfunction "2_2") (pintype "passive"))
      (node (ref "R74") (pin "1") (pinfunction "1_1") (pintype "passive"))
      (node (ref "R83") (pin "2") (pinfunction "2_2") (pintype "passive"))
      (node (ref "R86") (pin "1") (pinfunction "1_1") (pintype "passive"))
      (node (ref "U11") (pin "4") (pinfunction "GND1_4") (pintype "power_in"))
      (node (ref "U12") (pin "4") (pinfunction "GND1_4") (pintype "power_in"))
      (node (ref "U14") (pin "4") (pinfunction "GND1_4") (pintype "power_in"))
    )
    (net (code "18") (name "NEUTRAL") (class "Default")
      (node (ref "J14") (pin "2") (pinfunction "2_2") (pintype "passive"))
      (node (ref "J15") (pin "2") (pinfunction "2_2") (pintype "passive"))
      (node (ref "J16") (pin "2") (pinfunction "2_2") (pintype "passive"))
      (node (ref "R59") (pin "1") (pinfunction "1_1") (pintype "passive"))
      (node (ref "R60") (pin "1") (pinfunction "1_1") (pintype "passive"))
      (node (ref "R61") (pin "1") (pinfunction "1_1") (pintype "passive"))
      (node (ref "R71") (pin "1") (pinfunction "1_1") (pintype "passive"))
      (node (ref "R72") (pin "1") (pinfunction "1_1") (pintype "passive"))
      (node (ref "R73") (pin "1") (pinfunction "1_1") (pintype "passive"))
      (node (ref "R83") (pin "1") (pinfunction "1_1") (pintype "passive"))
      (node (ref "R84") (pin "1") (pinfunction "1_1") (pintype "passive"))
      (node (ref "R85") (pin "1") (pinfunction "1_1") (pintype "passive"))
    )
    (net (code "19") (name "Net-(D15-C)") (class "Default")
      (node (ref "C68") (pin "1") (pinfunction "1_1") (pintype "passive"))
      (node (ref "D15") (pin "3") (pinfunction "C_3") (pintype "passive"))
      (node (ref "R107") (pin "1") (pinfunction "1_1") (pintype "passive"))
      (node (ref "R89") (pin "2") (pinfunction "2_2") (pintype "passive"))
      (node (ref "U14") (pin "2") (pinfunction "VINP_2") (pintype "input"))
    )
    (net (code "20") (name "Net-(D16-C)") (class "Default")
      (node (ref "C68") (pin "2") (pinfunction "2_2") (pintype "passive"))
      (node (ref "D16") (pin "3") (pinfunction "C_3") (pintype "passive"))
      (node (ref "R86") (pin "2") (pinfunction "2_2") (pintype "passive"))
      (node (ref "U14") (pin "3") (pinfunction "VINN_3") (pintype "input"))
    )
    (net (code "21") (name "Net-(D17-C)") (class "Default")
      (node (ref "C61") (pin "2") (pinfunction "2_2") (pintype "passive"))
      (node (ref "D17") (pin "3") (pinfunction "C_3") (pintype "passive"))
      (node (ref "R74") (pin "2") (pinfunction "2_2") (pintype "passive"))
      (node (ref "U12") (pin "3") (pinfunction "VINN_3") (pintype "input"))
    )
    (net (code "22") (name "Net-(D18-C)") (class "Default")
      (node (ref "C61") (pin "1") (pinfunction "1_1") (pintype "passive"))
      (node (ref "D18") (pin "3") (pinfunction "C_3") (pintype "passive"))
      (node (ref "R77") (pin "2") (pinfunction "2_2") (pintype "passive"))
      (node (ref "R97") (pin "1") (pinfunction "1_1") (pintype "passive"))
      (node (ref "U12") (pin "2") (pinfunction "VINP_2") (pintype "input"))
    )
    (net (code "23") (name "Net-(D19-C)") (class "Default")
      (node (ref "C55") (pin "2") (pinfunction "2_2") (pintype "passive"))
      (node (ref "D19") (pin "3") (pinfunction "C_3") (pintype "passive"))
      (node (ref "R63") (pin "2") (pinfunction "2_2") (pintype "passive"))
      (node (ref "U11") (pin "3") (pinfunction "VINN_3") (pintype "input"))
    )
    (net (code "24") (name "Net-(D20-C)") (class "Default")
      (node (ref "C55") (pin "1") (pinfunction "1_1") (pintype "passive"))
      (node (ref "D20") (pin "3") (pinfunction "C_3") (pintype "passive"))
      (node (ref "R52") (pin "1") (pinfunction "1_1") (pintype "passive"))
      (node (ref "R65") (pin "2") (pinfunction "2_2") (pintype "passive"))
      (node (ref "U11") (pin "2") (pinfunction "VINP_2") (pintype "input"))
    )
    (net (code "25") (name "Net-(FB9-Pad1)") (class "Default")
      (node (ref "FB9") (pin "1") (pinfunction "1_1") (pintype "passive"))
      (node (ref "J14") (pin "1") (pinfunction "1_1") (pintype "passive"))
    )
    (net (code "26") (name "Net-(FB9-Pad2)") (class "Default")
      (node (ref "FB9") (pin "2") (pinfunction "2_2") (pintype "passive"))
      (node (ref "R67") (pin "1") (pinfunction "1_1") (pintype "passive"))
    )
    (net (code "27") (name "Net-(FB11-Pad1)") (class "Default")
      (node (ref "FB11") (pin "1") (pinfunction "1_1") (pintype "passive"))
      (node (ref "J15") (pin "1") (pinfunction "1_1") (pintype "passive"))
    )
    (net (code "28") (name "Net-(FB11-Pad2)") (class "Default")
      (node (ref "FB11") (pin "2") (pinfunction "2_2") (pintype "passive"))
      (node (ref "R79") (pin "1") (pinfunction "1_1") (pintype "passive"))
    )
    (net (code "29") (name "Net-(FB12-Pad1)") (class "Default")
      (node (ref "FB12") (pin "1") (pinfunction "1_1") (pintype "passive"))
      (node (ref "J16") (pin "1") (pinfunction "1_1") (pintype "passive"))
    )
    (net (code "30") (name "Net-(FB12-Pad2)") (class "Default")
      (node (ref "FB12") (pin "2") (pinfunction "2_2") (pintype "passive"))
      (node (ref "R90") (pin "1") (pinfunction "1_1") (pintype "passive"))
    )
    (net (code "31") (name "Net-(R60-Pad2)") (class "Default")
      (node (ref "R60") (pin "2") (pinfunction "2_2") (pintype "passive"))
      (node (ref "R61") (pin "2") (pinfunction "2_2") (pintype "passive"))
      (node (ref "R65") (pin "1") (pinfunction "1_1") (pintype "passive"))
      (node (ref "R70") (pin "2") (pinfunction "2_2") (pintype "passive"))
    )
    (net (code "32") (name "Net-(R67-Pad2)") (class "Default")
      (node (ref "R67") (pin "2") (pinfunction "2_2") (pintype "passive"))
      (node (ref "R68") (pin "1") (pinfunction "1_1") (pintype "passive"))
    )
    (net (code "33") (name "Net-(R68-Pad2)") (class "Default")
      (node (ref "R68") (pin "2") (pinfunction "2_2") (pintype "passive"))
      (node (ref "R69") (pin "1") (pinfunction "1_1") (pintype "passive"))
    )
    (net (code "34") (name "Net-(R69-Pad2)") (class "Default")
      (node (ref "R69") (pin "2") (pinfunction "2_2") (pintype "passive"))
      (node (ref "R70") (pin "1") (pinfunction "1_1") (pintype "passive"))
    )
    (net (code "35") (name "Net-(R72-Pad2)") (class "Default")
      (node (ref "R72") (pin "2") (pinfunction "2_2") (pintype "passive"))
      (node (ref "R73") (pin "2") (pinfunction "2_2") (pintype "passive"))
      (node (ref "R77") (pin "1") (pinfunction "1_1") (pintype "passive"))
      (node (ref "R82") (pin "2") (pinfunction "2_2") (pintype "passive"))
    )
    (net (code "36") (name "Net-(R79-Pad2)") (class "Default")
      (node (ref "R79") (pin "2") (pinfunction "2_2") (pintype "passive"))
      (node (ref "R80") (pin "1") (pinfunction "1_1") (pintype "passive"))
    )
    (net (code "37") (name "Net-(R80-Pad2)") (class "Default")
      (node (ref "R80") (pin "2") (pinfunction "2_2") (pintype "passive"))
      (node (ref "R81") (pin "1") (pinfunction "1_1") (pintype "passive"))
    )
    (net (code "38") (name "Net-(R81-Pad2)") (class "Default")
      (node (ref "R81") (pin "2") (pinfunction "2_2") (pintype "passive"))
      (node (ref "R82") (pin "1") (pinfunction "1_1") (pintype "passive"))
    )
    (net (code "39") (name "Net-(R84-Pad2)") (class "Default")
      (node (ref "R84") (pin "2") (pinfunction "2_2") (pintype "passive"))
      (node (ref "R85") (pin "2") (pinfunction "2_2") (pintype "passive"))
      (node (ref "R89") (pin "1") (pinfunction "1_1") (pintype "passive"))
      (node (ref "R93") (pin "2") (pinfunction "2_2") (pintype "passive"))
    )
    (net (code "40") (name "Net-(R90-Pad2)") (class "Default")
      (node (ref "R90") (pin "2") (pinfunction "2_2") (pintype "passive"))
      (node (ref "R91") (pin "1") (pinfunction "1_1") (pintype "passive"))
    )
    (net (code "41") (name "Net-(R91-Pad2)") (class "Default")
      (node (ref "R91") (pin "2") (pinfunction "2_2") (pintype "passive"))
      (node (ref "R92") (pin "1") (pinfunction "1_1") (pintype "passive"))
    )
    (net (code "42") (name "Net-(R92-Pad2)") (class "Default")
      (node (ref "R92") (pin "2") (pinfunction "2_2") (pintype "passive"))
      (node (ref "R93") (pin "1") (pinfunction "1_1") (pintype "passive"))
    )
    (net (code "43") (name "Net-(U11-VOUTN)") (class "Default")
      (node (ref "R64") (pin "1") (pinfunction "1_1") (pintype "passive"))
      (node (ref "U11") (pin "6") (pinfunction "VOUTN_6") (pintype "output"))
    )
    (net (code "44") (name "Net-(U11-VOUTP)") (class "Default")
      (node (ref "R66") (pin "1") (pinfunction "1_1") (pintype "passive"))
      (node (ref "U11") (pin "7") (pinfunction "VOUTP_7") (pintype "output"))
    )
    (net (code "45") (name "Net-(U12-VOUTN)") (class "Default")
      (node (ref "R75") (pin "1") (pinfunction "1_1") (pintype "passive"))
      (node (ref "U12") (pin "6") (pinfunction "VOUTN_6") (pintype "output"))
    )
    (net (code "46") (name "Net-(U12-VOUTP)") (class "Default")
      (node (ref "R78") (pin "1") (pinfunction "1_1") (pintype "passive"))
      (node (ref "U12") (pin "7") (pinfunction "VOUTP_7") (pintype "output"))
    )
    (net (code "47") (name "Net-(U14-VOUTN)") (class "Default")
      (node (ref "R87") (pin "1") (pinfunction "1_1") (pintype "passive"))
      (node (ref "U14") (pin "6") (pinfunction "VOUTN_6") (pintype "output"))
    )
    (net (code "48") (name "Net-(U14-VOUTP)") (class "Default")
      (node (ref "R88") (pin "1") (pinfunction "1_1") (pintype "passive"))
      (node (ref "U14") (pin "7") (pinfunction "VOUTP_7") (pintype "output"))
    )
  )
)
